# USB_Interface.net
KiCad netlist of a schematic drawn in Altium Designer
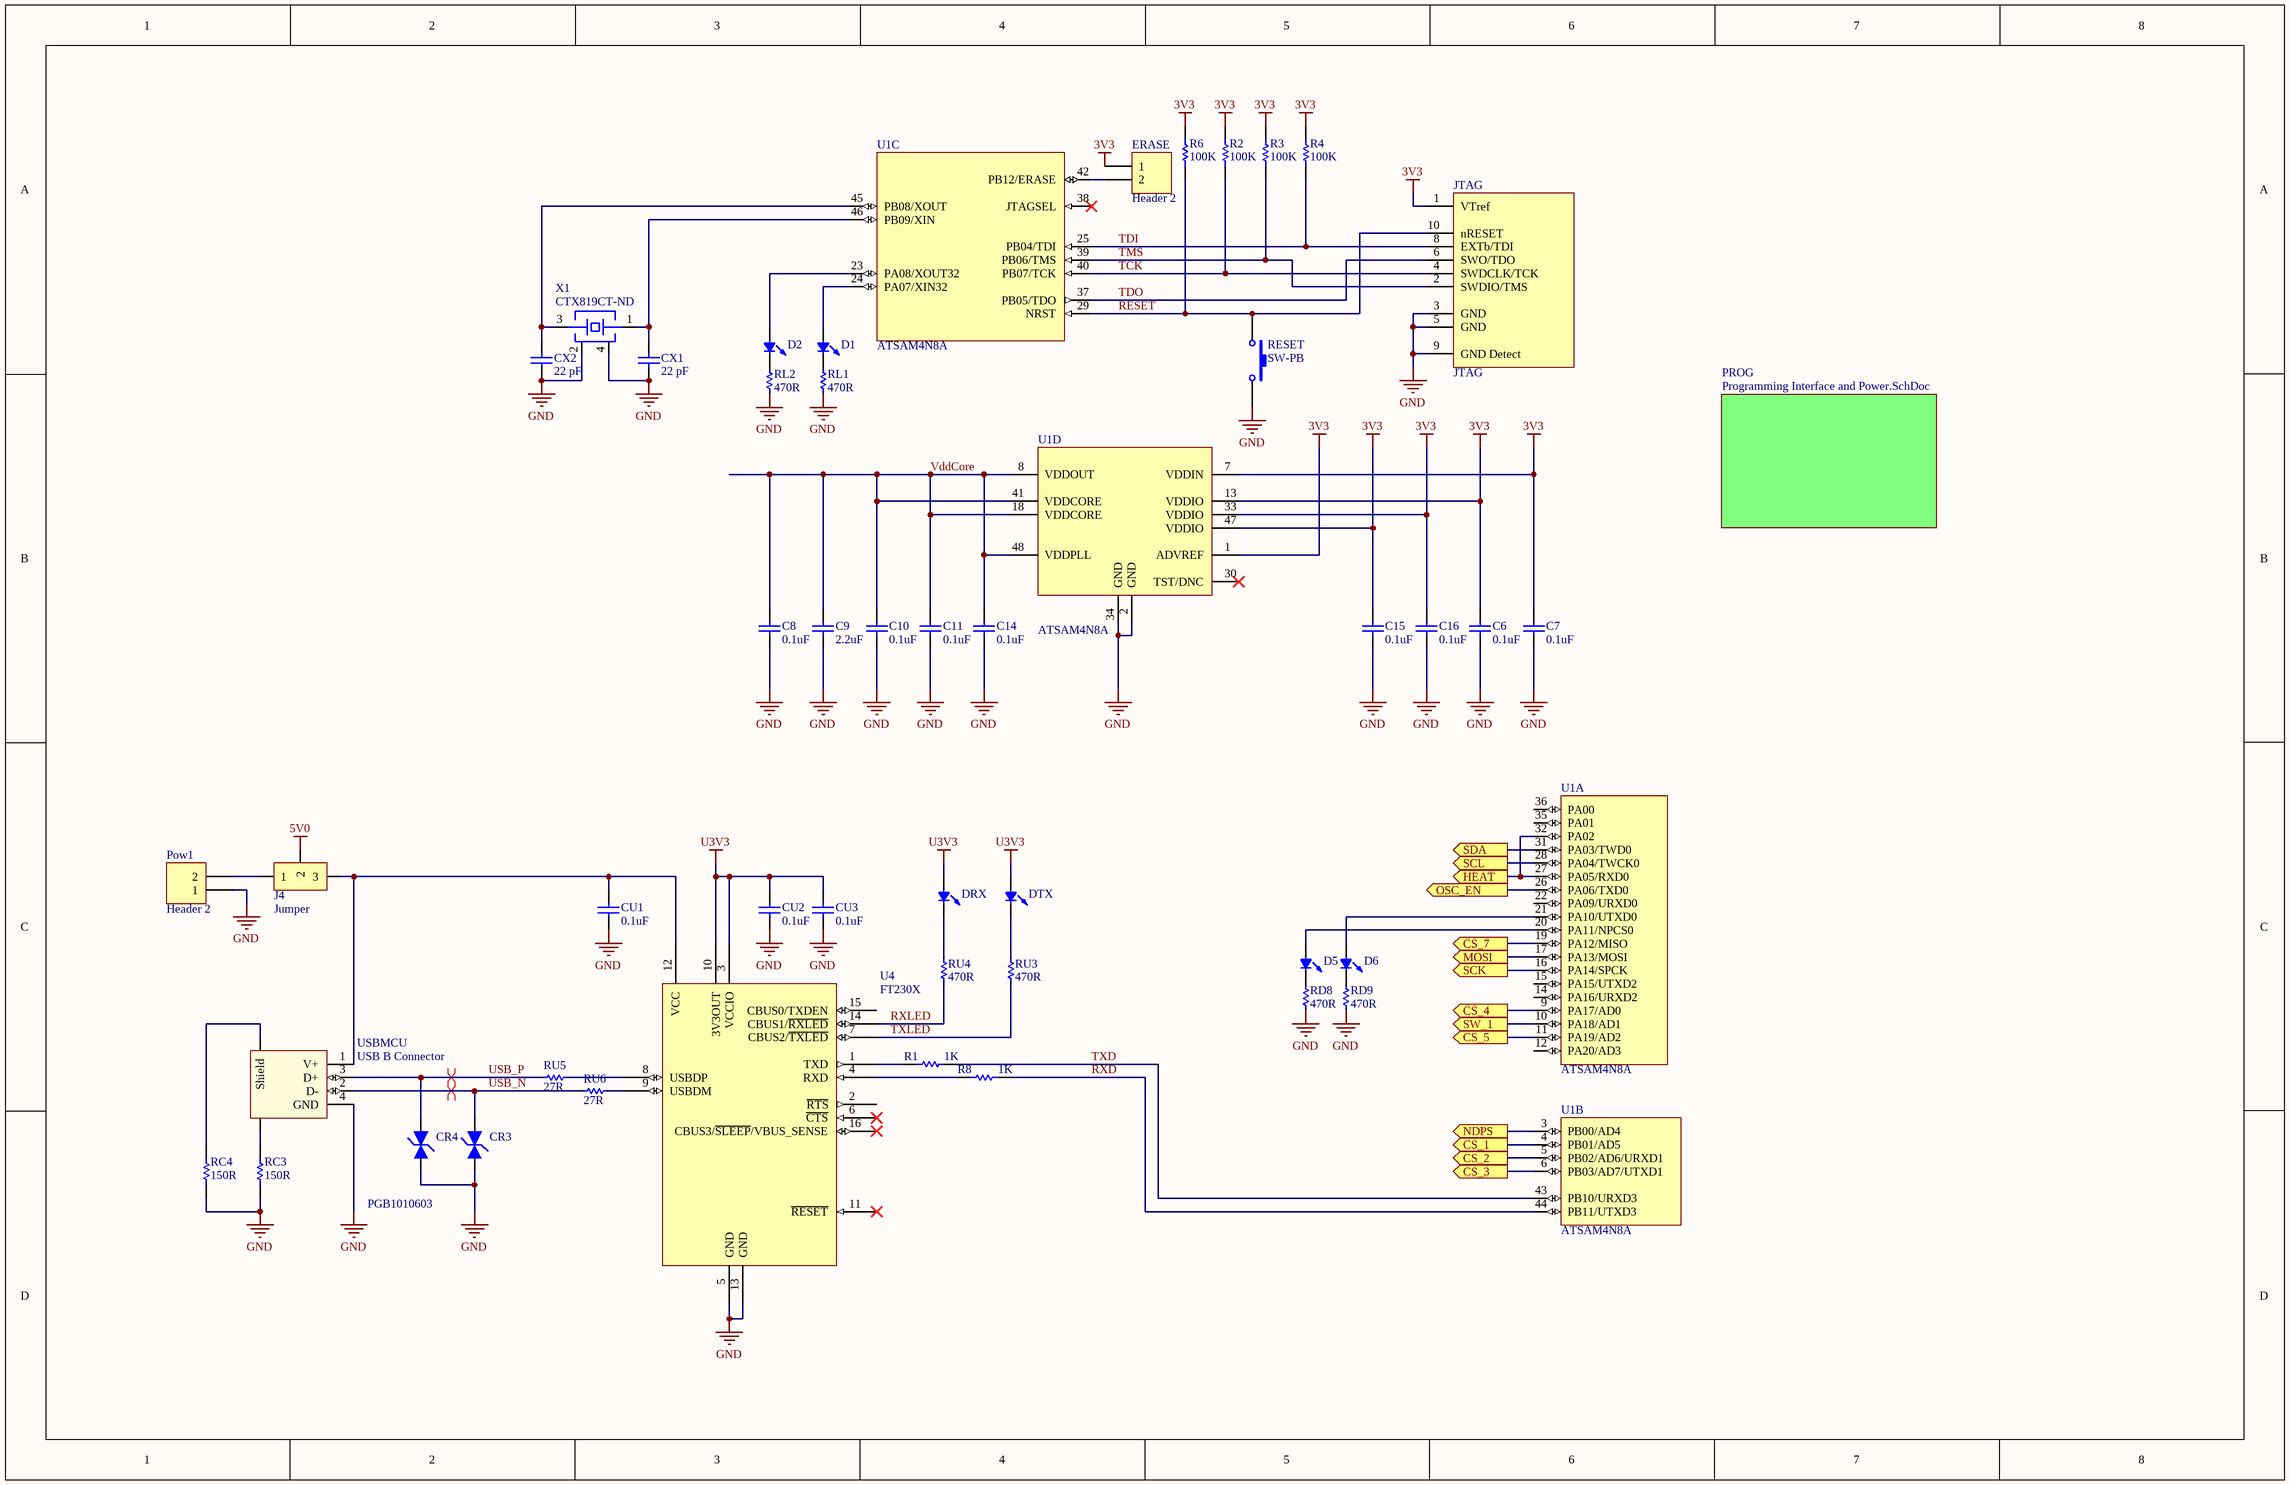
[diagram p0: USB Interface.SchDoc]

(export (version "E")
  (design (tool "Eeschema 10.0.6"))
  (components
    (comp (ref "C6")
      (value "0.1uF")
      (footprint "0603C")
      (description "Capacitor (Semiconductor SIM Model)")
      (fields (field (name "Comment") "Cap Semi") (field (name "PUBLISHER") "Altium Limited"))
      (libsource (lib "Miscellaneous Devices") (part "Cap Semi"))
    )
    (comp (ref "C7")
      (value "0.1uF")
      (footprint "0603C")
      (description "Capacitor (Semiconductor SIM Model)")
      (fields (field (name "Comment") "Cap Semi") (field (name "PUBLISHER") "Altium Limited"))
      (libsource (lib "Miscellaneous Devices") (part "Cap Semi"))
    )
    (comp (ref "C8")
      (value "0.1uF")
      (footprint "0603C")
      (description "Capacitor (Semiconductor SIM Model)")
      (fields (field (name "Comment") "Cap Semi") (field (name "PUBLISHER") "Altium Limited"))
      (libsource (lib "Miscellaneous Devices") (part "Cap Semi"))
    )
    (comp (ref "C9")
      (value "2.2uF")
      (footprint "1206C")
      (description "Capacitor (Semiconductor SIM Model)")
      (fields (field (name "Comment") "Cap Semi") (field (name "PUBLISHER") "Altium Limited"))
      (libsource (lib "Miscellaneous Devices") (part "Cap Semi"))
    )
    (comp (ref "C10")
      (value "0.1uF")
      (footprint "0603C")
      (description "Capacitor (Semiconductor SIM Model)")
      (fields (field (name "Comment") "Cap Semi") (field (name "PUBLISHER") "Altium Limited"))
      (libsource (lib "Miscellaneous Devices") (part "Cap Semi"))
    )
    (comp (ref "C11")
      (value "0.1uF")
      (footprint "0603C")
      (description "Capacitor (Semiconductor SIM Model)")
      (fields (field (name "Comment") "Cap Semi") (field (name "PUBLISHER") "Altium Limited"))
      (libsource (lib "Miscellaneous Devices") (part "Cap Semi"))
    )
    (comp (ref "C14")
      (value "0.1uF")
      (footprint "0603C")
      (description "Capacitor (Semiconductor SIM Model)")
      (fields (field (name "Comment") "Cap Semi") (field (name "PUBLISHER") "Altium Limited"))
      (libsource (lib "Miscellaneous Devices") (part "Cap Semi"))
    )
    (comp (ref "C15")
      (value "0.1uF")
      (footprint "0603C")
      (description "Capacitor (Semiconductor SIM Model)")
      (fields (field (name "Comment") "Cap Semi") (field (name "PUBLISHER") "Altium Limited"))
      (libsource (lib "Miscellaneous Devices") (part "Cap Semi"))
    )
    (comp (ref "C16")
      (value "0.1uF")
      (footprint "0603C")
      (description "Capacitor (Semiconductor SIM Model)")
      (fields (field (name "Comment") "Cap Semi") (field (name "PUBLISHER") "Altium Limited"))
      (libsource (lib "Miscellaneous Devices") (part "Cap Semi"))
    )
    (comp (ref "CR3")
      (value "PGB1010603")
      (footprint "0603PG")
      (description "PulseGuard® Lead-Free 0603 Surface Mount Polymeric ESD Suppressors")
      (libsource (lib "DAQ System") (part "PGB1010603"))
    )
    (comp (ref "CR4")
      (value "PGB1010603")
      (footprint "0603PG")
      (description "PulseGuard® Lead-Free 0603 Surface Mount Polymeric ESD Suppressors")
      (libsource (lib "DAQ System") (part "PGB1010603"))
    )
    (comp (ref "CU1")
      (value "0.1uF")
      (footprint "0603C")
      (description "Capacitor (Semiconductor SIM Model)")
      (fields (field (name "Comment") "Cap Semi") (field (name "PUBLISHER") "Altium Limited"))
      (libsource (lib "Miscellaneous Devices") (part "Cap Semi"))
    )
    (comp (ref "CU2")
      (value "0.1uF")
      (footprint "0603C")
      (description "Capacitor (Semiconductor SIM Model)")
      (fields (field (name "Comment") "Cap Semi") (field (name "PUBLISHER") "Altium Limited"))
      (libsource (lib "Miscellaneous Devices") (part "Cap Semi"))
    )
    (comp (ref "CU3")
      (value "0.1uF")
      (footprint "0603C")
      (description "Capacitor (Semiconductor SIM Model)")
      (fields (field (name "Comment") "Cap Semi") (field (name "PUBLISHER") "Altium Limited"))
      (libsource (lib "Miscellaneous Devices") (part "Cap Semi"))
    )
    (comp (ref "CX1")
      (value "22 pF")
      (footprint "0603C")
      (description "Capacitor (Semiconductor SIM Model)")
      (fields (field (name "Comment") "Cap Semi") (field (name "PUBLISHER") "Altium Limited"))
      (libsource (lib "Miscellaneous Devices") (part "Cap Semi"))
    )
    (comp (ref "CX2")
      (value "22 pF")
      (footprint "0603C")
      (description "Capacitor (Semiconductor SIM Model)")
      (fields (field (name "Comment") "Cap Semi") (field (name "PUBLISHER") "Altium Limited"))
      (libsource (lib "Miscellaneous Devices") (part "Cap Semi"))
    )
    (comp (ref "D1")
      (value "LED0")
      (footprint "T1 LED")
      (description "T 1 3/4 LED")
      (fields (field (name "PUBLISHER") "Altium Limited"))
      (libsource (lib "Miscellaneous Devices") (part "LED0"))
    )
    (comp (ref "D2")
      (value "LED0")
      (footprint "T1 LED")
      (description "T 1 3/4 LED")
      (fields (field (name "PUBLISHER") "Altium Limited"))
      (libsource (lib "Miscellaneous Devices") (part "LED0"))
    )
    (comp (ref "D5")
      (value "LED0")
      (footprint "T1 LED")
      (description "T 1 3/4 LED")
      (fields (field (name "PUBLISHER") "Altium Limited"))
      (libsource (lib "Miscellaneous Devices") (part "LED0"))
    )
    (comp (ref "D6")
      (value "LED0")
      (footprint "T1 LED")
      (description "T 1 3/4 LED")
      (fields (field (name "PUBLISHER") "Altium Limited"))
      (libsource (lib "Miscellaneous Devices") (part "LED0"))
    )
    (comp (ref "DRX")
      (value "LED0")
      (footprint "T1 LED")
      (description "T 1 3/4 LED")
      (fields (field (name "PUBLISHER") "Altium Limited"))
      (libsource (lib "Miscellaneous Devices") (part "LED0"))
    )
    (comp (ref "DTX")
      (value "LED0")
      (footprint "T1 LED")
      (description "T 1 3/4 LED")
      (fields (field (name "PUBLISHER") "Altium Limited"))
      (libsource (lib "Miscellaneous Devices") (part "LED0"))
    )
    (comp (ref "ERASE")
      (value "Header 2")
      (footprint "HDR1X2")
      (description "Header, 2-Pin")
      (fields (field (name "PUBLISHER") "Altium Limited"))
      (libsource (lib "") (part "Header 2_1"))
    )
    (comp (ref "J4")
      (value "Jumper")
      (footprint "HDR1X3")
      (description "Jumper - 3-Pin")
      (fields (field (name "PUBLISHER") "Altium Limited"))
      (libsource (lib "Miscellaneous Connectors") (part "Jumper - 3 Pin"))
    )
    (comp (ref "JTAG")
      (value "JTAG")
      (footprint "MHDR2X5")
      (description "ARM 10-Pin JTAG Interface")
      (libsource (lib "Connectors") (part "ARM JTAG-10"))
    )
    (comp (ref "Pow1")
      (value "Header 2")
      (footprint "AMPModu MTE 2 Pin Right Angle PCB-Locking Shrouded Header")
      (description "Header, 2-Pin")
      (fields (field (name "PUBLISHER") "Altium Limited"))
      (libsource (lib "Miscellaneous Connectors") (part "Header 2"))
    )
    (comp (ref "R1")
      (value "1K")
      (footprint "0603R")
      (description "Semiconductor Resistor")
      (fields (field (name "Comment") "Res Semi") (field (name "PUBLISHER") "Altium Limited"))
      (libsource (lib "Miscellaneous Devices") (part "Res Semi"))
    )
    (comp (ref "R2")
      (value "100K")
      (footprint "0603R")
      (description "Semiconductor Resistor")
      (fields (field (name "Comment") "Res Semi") (field (name "PUBLISHER") "Altium Limited"))
      (libsource (lib "Miscellaneous Devices") (part "Res Semi"))
    )
    (comp (ref "R3")
      (value "100K")
      (footprint "0603R")
      (description "Semiconductor Resistor")
      (fields (field (name "Comment") "Res Semi") (field (name "PUBLISHER") "Altium Limited"))
      (libsource (lib "Miscellaneous Devices") (part "Res Semi"))
    )
    (comp (ref "R4")
      (value "100K")
      (footprint "0603R")
      (description "Semiconductor Resistor")
      (fields (field (name "Comment") "Res Semi") (field (name "PUBLISHER") "Altium Limited"))
      (libsource (lib "Miscellaneous Devices") (part "Res Semi"))
    )
    (comp (ref "R6")
      (value "100K")
      (footprint "0603R")
      (description "Semiconductor Resistor")
      (fields (field (name "Comment") "Res Semi") (field (name "PUBLISHER") "Altium Limited"))
      (libsource (lib "Miscellaneous Devices") (part "Res Semi"))
    )
    (comp (ref "R8")
      (value "1K")
      (footprint "0603R")
      (description "Semiconductor Resistor")
      (fields (field (name "Comment") "Res Semi") (field (name "PUBLISHER") "Altium Limited"))
      (libsource (lib "Miscellaneous Devices") (part "Res Semi"))
    )
    (comp (ref "RC3")
      (value "150R")
      (footprint "1206R")
      (description "Semiconductor Resistor")
      (fields (field (name "Comment") "Res Semi") (field (name "PUBLISHER") "Altium Limited"))
      (libsource (lib "Miscellaneous Devices") (part "Res Semi"))
    )
    (comp (ref "RC4")
      (value "150R")
      (footprint "1206R")
      (description "Semiconductor Resistor")
      (fields (field (name "Comment") "Res Semi") (field (name "PUBLISHER") "Altium Limited"))
      (libsource (lib "Miscellaneous Devices") (part "Res Semi"))
    )
    (comp (ref "RD8")
      (value "470R")
      (footprint "0603R")
      (description "Semiconductor Resistor")
      (fields (field (name "Comment") "Res Semi Small") (field (name "PUBLISHER") "Altium Limited"))
      (libsource (lib "Miscellaneous Devices") (part "Res Semi Small"))
    )
    (comp (ref "RD9")
      (value "470R")
      (footprint "0603R")
      (description "Semiconductor Resistor")
      (fields (field (name "Comment") "Res Semi Small") (field (name "PUBLISHER") "Altium Limited"))
      (libsource (lib "Miscellaneous Devices") (part "Res Semi Small"))
    )
    (comp (ref "RESET")
      (value "SW-PB")
      (footprint "TL3302BF180QG/TR")
      (description "Switch")
      (fields (field (name "PUBLISHER") "Altium Limited"))
      (libsource (lib "Miscellaneous Devices") (part "SW-PB"))
    )
    (comp (ref "RL1")
      (value "470R")
      (footprint "0603R")
      (description "Semiconductor Resistor")
      (fields (field (name "Comment") "Res Semi Small") (field (name "PUBLISHER") "Altium Limited"))
      (libsource (lib "Miscellaneous Devices") (part "Res Semi Small"))
    )
    (comp (ref "RL2")
      (value "470R")
      (footprint "0603R")
      (description "Semiconductor Resistor")
      (fields (field (name "Comment") "Res Semi Small") (field (name "PUBLISHER") "Altium Limited"))
      (libsource (lib "Miscellaneous Devices") (part "Res Semi Small"))
    )
    (comp (ref "RU3")
      (value "470R")
      (footprint "0603R")
      (description "Semiconductor Resistor")
      (fields (field (name "Comment") "Res Semi Small") (field (name "PUBLISHER") "Altium Limited"))
      (libsource (lib "Miscellaneous Devices") (part "Res Semi Small"))
    )
    (comp (ref "RU4")
      (value "470R")
      (footprint "0603R")
      (description "Semiconductor Resistor")
      (fields (field (name "Comment") "Res Semi Small") (field (name "PUBLISHER") "Altium Limited"))
      (libsource (lib "Miscellaneous Devices") (part "Res Semi Small"))
    )
    (comp (ref "RU5")
      (value "27R")
      (footprint "0603R")
      (description "Semiconductor Resistor")
      (fields (field (name "Comment") "Res Semi Small") (field (name "PUBLISHER") "Altium Limited"))
      (libsource (lib "Miscellaneous Devices") (part "Res Semi Small"))
    )
    (comp (ref "RU6")
      (value "27R")
      (footprint "0603R")
      (description "Semiconductor Resistor")
      (fields (field (name "Comment") "Res Semi Small") (field (name "PUBLISHER") "Altium Limited"))
      (libsource (lib "Miscellaneous Devices") (part "Res Semi Small"))
    )
    (comp (ref "U1")
      (value "ATSAM4N8A")
      (footprint "TSQFP50P900X900-48N")
      (description "SAM4N ARM Cortex-M4 Microcontrollers")
      (libsource (lib "ICs") (part "ATSAM4N8A"))
    )
    (comp (ref "U4")
      (value "FT230X")
      (footprint "SOP635P600-16AN")
      (description "USB To Basic Serial Bridge IC")
      (libsource (lib "ICs") (part "FT230X"))
    )
    (comp (ref "USBMCU")
      (value "USB B Connector")
      (footprint "USB Connector (type B)")
      (libsource (lib "DAQ Sstem") (part "USB B connector - Through hole"))
    )
    (comp (ref "X1")
      (value "CTX819CT-ND")
      (footprint "Abracon ABM3B Crystal")
      (description "16 MHz Micro SMT Crystal")
      (libsource (lib "Unsorted") (part "SMT Crystal"))
    )
  )
  (nets
    (net (code "1") (name "/CS_1") (class "Default")
      (node (ref "U1") (pin "4") (pinfunction "PB01/AD5_4") (pintype "bidirectional"))
    )
    (net (code "2") (name "/CS_2") (class "Default")
      (node (ref "U1") (pin "5") (pinfunction "PB02/AD6/URXD1_5") (pintype "bidirectional"))
    )
    (net (code "3") (name "/CS_3") (class "Default")
      (node (ref "U1") (pin "6") (pinfunction "PB03/AD7/UTXD1_6") (pintype "bidirectional"))
    )
    (net (code "4") (name "/CS_4") (class "Default")
      (node (ref "U1") (pin "9") (pinfunction "PA17/AD0_9") (pintype "bidirectional"))
    )
    (net (code "5") (name "/CS_5") (class "Default")
      (node (ref "U1") (pin "11") (pinfunction "PA19/AD2_11") (pintype "bidirectional"))
    )
    (net (code "6") (name "/CS_7") (class "Default")
      (node (ref "U1") (pin "19") (pinfunction "PA12/MISO_19") (pintype "bidirectional"))
    )
    (net (code "7") (name "/HEAT") (class "Default")
      (node (ref "U1") (pin "27") (pinfunction "PA05/RXD0_27") (pintype "bidirectional"))
      (node (ref "U1") (pin "32") (pinfunction "PA02_32") (pintype "bidirectional"))
    )
    (net (code "8") (name "/MOSI") (class "Default")
      (node (ref "U1") (pin "17") (pinfunction "PA13/MOSI_17") (pintype "bidirectional"))
    )
    (net (code "9") (name "/NDPS") (class "Default")
      (node (ref "U1") (pin "3") (pinfunction "PB00/AD4_3") (pintype "bidirectional"))
    )
    (net (code "10") (name "/OSC_EN") (class "Default")
      (node (ref "U1") (pin "26") (pinfunction "PA06/TXD0_26") (pintype "bidirectional"))
    )
    (net (code "11") (name "/RESET") (class "Default")
      (node (ref "JTAG") (pin "10") (pinfunction "nRESET_10") (pintype "power_in"))
      (node (ref "R6") (pin "1") (pinfunction "1_1") (pintype "passive"))
      (node (ref "RESET") (pin "1") (pinfunction "1_1") (pintype "passive"))
      (node (ref "U1") (pin "29") (pinfunction "NRST_29") (pintype "input"))
    )
    (net (code "12") (name "/RXD") (class "Default")
      (node (ref "R8") (pin "2") (pinfunction "2_2") (pintype "passive"))
      (node (ref "U1") (pin "44") (pinfunction "PB11/UTXD3_44") (pintype "bidirectional"))
    )
    (net (code "13") (name "/RXLED") (class "Default")
      (node (ref "RU4") (pin "2") (pinfunction "2_2") (pintype "passive"))
      (node (ref "U4") (pin "14") (pinfunction "CBUS1/~{RXLED}_14") (pintype "bidirectional"))
    )
    (net (code "14") (name "/SCK") (class "Default")
      (node (ref "U1") (pin "16") (pinfunction "PA14/SPCK_16") (pintype "bidirectional"))
    )
    (net (code "15") (name "/SCL") (class "Default")
      (node (ref "U1") (pin "28") (pinfunction "PA04/TWCK0_28") (pintype "bidirectional"))
    )
    (net (code "16") (name "/SDA") (class "Default")
      (node (ref "U1") (pin "31") (pinfunction "PA03/TWD0_31") (pintype "bidirectional"))
    )
    (net (code "17") (name "/SW_1") (class "Default")
      (node (ref "U1") (pin "10") (pinfunction "PA18/AD1_10") (pintype "bidirectional"))
    )
    (net (code "18") (name "/TCK") (class "Default")
      (node (ref "JTAG") (pin "4") (pinfunction "SWDCLK/TCK_4") (pintype "power_in"))
      (node (ref "R2") (pin "1") (pinfunction "1_1") (pintype "passive"))
      (node (ref "U1") (pin "40") (pinfunction "PB07/TCK_40") (pintype "input"))
    )
    (net (code "19") (name "/TDI") (class "Default")
      (node (ref "JTAG") (pin "8") (pinfunction "EXTb/TDI_8") (pintype "power_in"))
      (node (ref "R4") (pin "1") (pinfunction "1_1") (pintype "passive"))
      (node (ref "U1") (pin "25") (pinfunction "PB04/TDI_25") (pintype "input"))
    )
    (net (code "20") (name "/TDO") (class "Default")
      (node (ref "JTAG") (pin "6") (pinfunction "SWO/TDO_6") (pintype "power_in"))
      (node (ref "U1") (pin "37") (pinfunction "PB05/TDO_37") (pintype "output"))
    )
    (net (code "21") (name "/TMS") (class "Default")
      (node (ref "JTAG") (pin "2") (pinfunction "SWDIO/TMS_2") (pintype "power_in"))
      (node (ref "R3") (pin "1") (pinfunction "1_1") (pintype "passive"))
      (node (ref "U1") (pin "39") (pinfunction "PB06/TMS_39") (pintype "input"))
    )
    (net (code "22") (name "/TXD") (class "Default")
      (node (ref "R1") (pin "2") (pinfunction "2_2") (pintype "passive"))
      (node (ref "U1") (pin "43") (pinfunction "PB10/URXD3_43") (pintype "bidirectional"))
    )
    (net (code "23") (name "/TXLED") (class "Default")
      (node (ref "RU3") (pin "2") (pinfunction "2_2") (pintype "passive"))
      (node (ref "U4") (pin "7") (pinfunction "CBUS2/~{TXLED}_7") (pintype "bidirectional"))
    )
    (net (code "24") (name "/USB_N") (class "Default")
      (node (ref "CR3") (pin "1") (pinfunction "1_1") (pintype "passive"))
      (node (ref "RU6") (pin "1") (pinfunction "1_1") (pintype "passive"))
      (node (ref "USBMCU") (pin "2") (pinfunction "D-_2") (pintype "bidirectional"))
    )
    (net (code "25") (name "/USB_P") (class "Default")
      (node (ref "CR4") (pin "1") (pinfunction "1_1") (pintype "passive"))
      (node (ref "RU5") (pin "1") (pinfunction "1_1") (pintype "passive"))
      (node (ref "USBMCU") (pin "3") (pinfunction "D+_3") (pintype "bidirectional"))
    )
    (net (code "26") (name "/VddCore") (class "Default")
      (node (ref "C10") (pin "2") (pinfunction "2_2") (pintype "passive"))
      (node (ref "C11") (pin "2") (pinfunction "2_2") (pintype "passive"))
      (node (ref "C14") (pin "2") (pinfunction "2_2") (pintype "passive"))
      (node (ref "C8") (pin "2") (pinfunction "2_2") (pintype "passive"))
      (node (ref "C9") (pin "2") (pinfunction "2_2") (pintype "passive"))
      (node (ref "U1") (pin "18") (pinfunction "VDDCORE_18") (pintype "power_in"))
      (node (ref "U1") (pin "41") (pinfunction "VDDCORE_41") (pintype "power_in"))
      (node (ref "U1") (pin "48") (pinfunction "VDDPLL_48") (pintype "power_in"))
      (node (ref "U1") (pin "8") (pinfunction "VDDOUT_8") (pintype "power_in"))
    )
    (net (code "27") (name "3V3") (class "Default")
      (node (ref "C15") (pin "2") (pinfunction "2_2") (pintype "passive"))
      (node (ref "C16") (pin "2") (pinfunction "2_2") (pintype "passive"))
      (node (ref "C6") (pin "2") (pinfunction "2_2") (pintype "passive"))
      (node (ref "C7") (pin "2") (pinfunction "2_2") (pintype "passive"))
      (node (ref "ERASE") (pin "1") (pinfunction "1_1") (pintype "passive"))
      (node (ref "JTAG") (pin "1") (pinfunction "VTref_1") (pintype "power_in"))
      (node (ref "R2") (pin "2") (pinfunction "2_2") (pintype "passive"))
      (node (ref "R3") (pin "2") (pinfunction "2_2") (pintype "passive"))
      (node (ref "R4") (pin "2") (pinfunction "2_2") (pintype "passive"))
      (node (ref "R6") (pin "2") (pinfunction "2_2") (pintype "passive"))
      (node (ref "U1") (pin "1") (pinfunction "ADVREF_1") (pintype "power_in"))
      (node (ref "U1") (pin "13") (pinfunction "VDDIO_13") (pintype "power_in"))
      (node (ref "U1") (pin "33") (pinfunction "VDDIO_33") (pintype "power_in"))
      (node (ref "U1") (pin "47") (pinfunction "VDDIO_47") (pintype "power_in"))
      (node (ref "U1") (pin "7") (pinfunction "VDDIN_7") (pintype "power_in"))
    )
    (net (code "28") (name "5V0") (class "Default")
      (node (ref "J4") (pin "2") (pinfunction "2_2") (pintype "passive"))
    )
    (net (code "29") (name "GND") (class "Default")
      (node (ref "C10") (pin "1") (pinfunction "1_1") (pintype "passive"))
      (node (ref "C11") (pin "1") (pinfunction "1_1") (pintype "passive"))
      (node (ref "C14") (pin "1") (pinfunction "1_1") (pintype "passive"))
      (node (ref "C15") (pin "1") (pinfunction "1_1") (pintype "passive"))
      (node (ref "C16") (pin "1") (pinfunction "1_1") (pintype "passive"))
      (node (ref "C6") (pin "1") (pinfunction "1_1") (pintype "passive"))
      (node (ref "C7") (pin "1") (pinfunction "1_1") (pintype "passive"))
      (node (ref "C8") (pin "1") (pinfunction "1_1") (pintype "passive"))
      (node (ref "C9") (pin "1") (pinfunction "1_1") (pintype "passive"))
      (node (ref "CR3") (pin "2") (pinfunction "2_2") (pintype "passive"))
      (node (ref "CR4") (pin "2") (pinfunction "2_2") (pintype "passive"))
      (node (ref "CU1") (pin "1") (pinfunction "1_1") (pintype "passive"))
      (node (ref "CU2") (pin "1") (pinfunction "1_1") (pintype "passive"))
      (node (ref "CU3") (pin "1") (pinfunction "1_1") (pintype "passive"))
      (node (ref "CX1") (pin "1") (pinfunction "1_1") (pintype "passive"))
      (node (ref "CX2") (pin "1") (pinfunction "1_1") (pintype "passive"))
      (node (ref "JTAG") (pin "3") (pinfunction "GND_3") (pintype "power_in"))
      (node (ref "JTAG") (pin "5") (pinfunction "GND_5") (pintype "power_in"))
      (node (ref "JTAG") (pin "9") (pinfunction "GND_Detect_9") (pintype "power_in"))
      (node (ref "Pow1") (pin "1") (pinfunction "1_1") (pintype "passive"))
      (node (ref "RC3") (pin "1") (pinfunction "1_1") (pintype "passive"))
      (node (ref "RC4") (pin "1") (pinfunction "1_1") (pintype "passive"))
      (node (ref "RD8") (pin "2") (pinfunction "2_2") (pintype "passive"))
      (node (ref "RD9") (pin "2") (pinfunction "2_2") (pintype "passive"))
      (node (ref "RESET") (pin "2") (pinfunction "2_2") (pintype "passive"))
      (node (ref "RL1") (pin "2") (pinfunction "2_2") (pintype "passive"))
      (node (ref "RL2") (pin "2") (pinfunction "2_2") (pintype "passive"))
      (node (ref "U1") (pin "2") (pinfunction "GND_2") (pintype "power_in"))
      (node (ref "U1") (pin "34") (pinfunction "GND_34") (pintype "power_in"))
      (node (ref "U4") (pin "13") (pinfunction "GND_13") (pintype "power_in"))
      (node (ref "U4") (pin "5") (pinfunction "GND_5") (pintype "power_in"))
      (node (ref "USBMCU") (pin "4") (pinfunction "GND_4") (pintype "power_in"))
      (node (ref "X1") (pin "2") (pinfunction "2_2") (pintype "passive"))
      (node (ref "X1") (pin "4") (pinfunction "4_4") (pintype "passive"))
    )
    (net (code "30") (name "Net-(D1-Pad2)") (class "Default")
      (node (ref "D1") (pin "2") (pinfunction "2_2") (pintype "passive"))
      (node (ref "RL1") (pin "1") (pinfunction "1_1") (pintype "passive"))
    )
    (net (code "31") (name "Net-(D2-Pad2)") (class "Default")
      (node (ref "D2") (pin "2") (pinfunction "2_2") (pintype "passive"))
      (node (ref "RL2") (pin "1") (pinfunction "1_1") (pintype "passive"))
    )
    (net (code "32") (name "Net-(D5-Pad2)") (class "Default")
      (node (ref "D5") (pin "2") (pinfunction "2_2") (pintype "passive"))
      (node (ref "RD8") (pin "1") (pinfunction "1_1") (pintype "passive"))
    )
    (net (code "33") (name "Net-(D6-Pad2)") (class "Default")
      (node (ref "D6") (pin "2") (pinfunction "2_2") (pintype "passive"))
      (node (ref "RD9") (pin "1") (pinfunction "1_1") (pintype "passive"))
    )
    (net (code "34") (name "Net-(DRX-Pad2)") (class "Default")
      (node (ref "DRX") (pin "2") (pinfunction "2_2") (pintype "passive"))
      (node (ref "RU4") (pin "1") (pinfunction "1_1") (pintype "passive"))
    )
    (net (code "35") (name "Net-(DTX-Pad2)") (class "Default")
      (node (ref "DTX") (pin "2") (pinfunction "2_2") (pintype "passive"))
      (node (ref "RU3") (pin "1") (pinfunction "1_1") (pintype "passive"))
    )
    (net (code "36") (name "Net-(J4-Pad1)") (class "Default")
      (node (ref "J4") (pin "1") (pinfunction "1_1") (pintype "passive"))
      (node (ref "Pow1") (pin "2") (pinfunction "2_2") (pintype "passive"))
    )
    (net (code "37") (name "Net-(U1A-PA10{slash}UTXD0)") (class "Default")
      (node (ref "D6") (pin "1") (pinfunction "1_1") (pintype "passive"))
      (node (ref "U1") (pin "21") (pinfunction "PA10/UTXD0_21") (pintype "bidirectional"))
    )
    (net (code "38") (name "Net-(U1A-PA11{slash}NPCS0)") (class "Default")
      (node (ref "D5") (pin "1") (pinfunction "1_1") (pintype "passive"))
      (node (ref "U1") (pin "20") (pinfunction "PA11/NPCS0_20") (pintype "bidirectional"))
    )
    (net (code "39") (name "Net-(U1C-PA07{slash}XIN32)") (class "Default")
      (node (ref "D1") (pin "1") (pinfunction "1_1") (pintype "passive"))
      (node (ref "U1") (pin "24") (pinfunction "PA07/XIN32_24") (pintype "bidirectional"))
    )
    (net (code "40") (name "Net-(U1C-PA08{slash}XOUT32)") (class "Default")
      (node (ref "D2") (pin "1") (pinfunction "1_1") (pintype "passive"))
      (node (ref "U1") (pin "23") (pinfunction "PA08/XOUT32_23") (pintype "bidirectional"))
    )
    (net (code "41") (name "Net-(U1C-PB08{slash}XOUT)") (class "Default")
      (node (ref "CX2") (pin "2") (pinfunction "2_2") (pintype "passive"))
      (node (ref "U1") (pin "45") (pinfunction "PB08/XOUT_45") (pintype "bidirectional"))
      (node (ref "X1") (pin "3") (pinfunction "3_3") (pintype "passive"))
    )
    (net (code "42") (name "Net-(U1C-PB09{slash}XIN)") (class "Default")
      (node (ref "CX1") (pin "2") (pinfunction "2_2") (pintype "passive"))
      (node (ref "U1") (pin "46") (pinfunction "PB09/XIN_46") (pintype "bidirectional"))
      (node (ref "X1") (pin "1") (pinfunction "1_1") (pintype "passive"))
    )
    (net (code "43") (name "Net-(U1C-PB12{slash}ERASE)") (class "Default")
      (node (ref "ERASE") (pin "2") (pinfunction "2_2") (pintype "passive"))
      (node (ref "U1") (pin "42") (pinfunction "PB12/ERASE_42") (pintype "bidirectional"))
    )
    (net (code "44") (name "Net-(U4-RXD)") (class "Default")
      (node (ref "R8") (pin "1") (pinfunction "1_1") (pintype "passive"))
      (node (ref "U4") (pin "4") (pinfunction "RXD_4") (pintype "input"))
    )
    (net (code "45") (name "Net-(U4-TXD)") (class "Default")
      (node (ref "R1") (pin "1") (pinfunction "1_1") (pintype "passive"))
      (node (ref "U4") (pin "1") (pinfunction "TXD_1") (pintype "output"))
    )
    (net (code "46") (name "Net-(U4-USBDM)") (class "Default")
      (node (ref "RU6") (pin "2") (pinfunction "2_2") (pintype "passive"))
      (node (ref "U4") (pin "9") (pinfunction "USBDM_9") (pintype "bidirectional"))
    )
    (net (code "47") (name "Net-(U4-USBDP)") (class "Default")
      (node (ref "RU5") (pin "2") (pinfunction "2_2") (pintype "passive"))
      (node (ref "U4") (pin "8") (pinfunction "USBDP_8") (pintype "bidirectional"))
    )
    (net (code "48") (name "Net-(U4-VCC)") (class "Default")
      (node (ref "CU1") (pin "2") (pinfunction "2_2") (pintype "passive"))
      (node (ref "J4") (pin "3") (pinfunction "3_3") (pintype "passive"))
      (node (ref "U4") (pin "12") (pinfunction "VCC_12") (pintype "power_in"))
      (node (ref "USBMCU") (pin "1") (pinfunction "V+_1") (pintype "power_in"))
    )
    (net (code "49") (name "Net-(USBMCU-Gnd)") (class "Default")
      (node (ref "RC3") (pin "2") (pinfunction "2_2") (pintype "passive"))
      (node (ref "USBMCU") (pin "5") (pinfunction "Gnd_5") (pintype "passive"))
    )
    (net (code "50") (name "Net-(USBMCU-Shield)") (class "Default")
      (node (ref "RC4") (pin "2") (pinfunction "2_2") (pintype "passive"))
      (node (ref "USBMCU") (pin "6") (pinfunction "Shield_6") (pintype "passive"))
    )
    (net (code "51") (name "U3V3") (class "Default")
      (node (ref "CU2") (pin "2") (pinfunction "2_2") (pintype "passive"))
      (node (ref "CU3") (pin "2") (pinfunction "2_2") (pintype "passive"))
      (node (ref "DRX") (pin "1") (pinfunction "1_1") (pintype "passive"))
      (node (ref "DTX") (pin "1") (pinfunction "1_1") (pintype "passive"))
      (node (ref "U4") (pin "10") (pinfunction "3V3OUT_10") (pintype "power_in"))
      (node (ref "U4") (pin "3") (pinfunction "VCCIO_3") (pintype "power_in"))
    )
    (net (code "52") (name "unconnected-(U1A-PA00-Pad36)") (class "Default")
      (node (ref "U1") (pin "36") (pinfunction "PA00_36") (pintype "bidirectional"))
    )
    (net (code "53") (name "unconnected-(U1A-PA01-Pad35)") (class "Default")
      (node (ref "U1") (pin "35") (pinfunction "PA01_35") (pintype "bidirectional"))
    )
    (net (code "54") (name "unconnected-(U1A-PA09{slash}URXD0-Pad22)") (class "Default")
      (node (ref "U1") (pin "22") (pinfunction "PA09/URXD0_22") (pintype "bidirectional"))
    )
    (net (code "55") (name "unconnected-(U1A-PA15{slash}UTXD2-Pad15)") (class "Default")
      (node (ref "U1") (pin "15") (pinfunction "PA15/UTXD2_15") (pintype "bidirectional"))
    )
    (net (code "56") (name "unconnected-(U1A-PA16{slash}URXD2-Pad14)") (class "Default")
      (node (ref "U1") (pin "14") (pinfunction "PA16/URXD2_14") (pintype "bidirectional"))
    )
    (net (code "57") (name "unconnected-(U1A-PA20{slash}AD3-Pad12)") (class "Default")
      (node (ref "U1") (pin "12") (pinfunction "PA20/AD3_12") (pintype "bidirectional"))
    )
    (net (code "58") (name "unconnected-(U1C-JTAGSEL-Pad38)") (class "Default")
      (node (ref "U1") (pin "38") (pinfunction "JTAGSEL_38") (pintype "input+no_connect"))
    )
    (net (code "59") (name "unconnected-(U1D-TST{slash}DNC-Pad30)") (class "Default")
      (node (ref "U1") (pin "30") (pinfunction "TST/DNC_30") (pintype "passive+no_connect"))
    )
    (net (code "60") (name "unconnected-(U4-CBUS0{slash}TXDEN-Pad15)") (class "Default")
      (node (ref "U4") (pin "15") (pinfunction "CBUS0/TXDEN_15") (pintype "bidirectional"))
    )
    (net (code "61") (name "unconnected-(U4-CBUS3{slash}~{SLEEP}{slash}VBUS_SENSE-Pad16)") (class "Default")
      (node (ref "U4") (pin "16") (pinfunction "CBUS3/~{SLEEP}/VBUS_SENSE_16") (pintype "bidirectional+no_connect"))
    )
    (net (code "62") (name "unconnected-(U4-CTS-Pad6)") (class "Default")
      (node (ref "U4") (pin "6") (pinfunction "CTS_6") (pintype "input+no_connect"))
    )
    (net (code "63") (name "unconnected-(U4-NC-Pad8)") (class "Default")
      (node (ref "U4") (pin "8") (pinfunction "NC_8") (pintype "passive"))
    )
    (net (code "64") (name "unconnected-(U4-NC-Pad24)") (class "Default")
      (node (ref "U4") (pin "24") (pinfunction "NC_24") (pintype "passive"))
    )
    (net (code "65") (name "unconnected-(U4-RTS-Pad2)") (class "Default")
      (node (ref "U4") (pin "2") (pinfunction "RTS_2") (pintype "output"))
    )
    (net (code "66") (name "unconnected-(U4-~{RESET}-Pad11)") (class "Default")
      (node (ref "U4") (pin "11") (pinfunction "~{RESET}_11") (pintype "input+no_connect"))
    )
  )
)
